# TP4056_18650.net
KiCad netlist of a schematic drawn in EAGLE
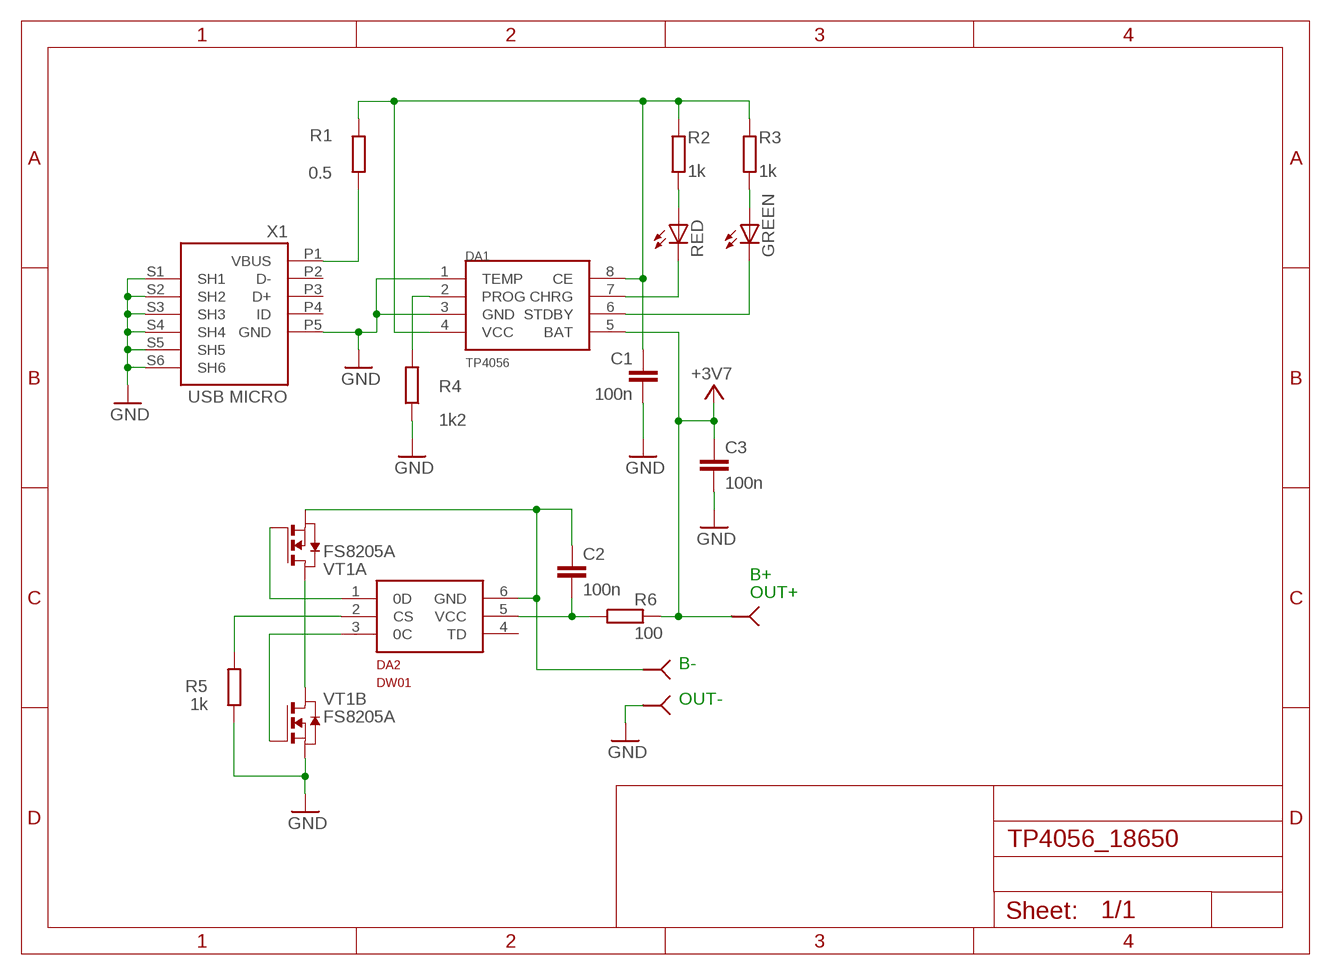
[diagram p0: schematic, sheet 1]

(export (version "E")
  (design (tool "Eeschema 10.0.6"))
  (components
    (comp (ref "B+")
      (value "B-")
      (footprint "eagle-import:PAD-")
      (libsource (lib "eagle-import") (part "B-"))
    )
    (comp (ref "B-")
      (value "B-")
      (footprint "eagle-import:PAD-")
      (libsource (lib "eagle-import") (part "B-"))
    )
    (comp (ref "C1")
      (value "100n")
      (footprint "eagle-import:C0805")
      (libsource (lib "eagle-import") (part "C-EUC0805"))
    )
    (comp (ref "C2")
      (value "100n")
      (footprint "eagle-import:C0805")
      (libsource (lib "eagle-import") (part "C-EUC0805"))
    )
    (comp (ref "C3")
      (value "100n")
      (footprint "eagle-import:C0805")
      (libsource (lib "eagle-import") (part "C-EUC0805"))
    )
    (comp (ref "DA1")
      (value "TP4056")
      (footprint "eagle-import:SOP-8")
      (libsource (lib "eagle-import") (part "TP4056"))
    )
    (comp (ref "DA2")
      (value "DW01A")
      (footprint "eagle-import:SOT23-6")
      (libsource (lib "eagle-import") (part "DW01"))
    )
    (comp (ref "GND")
      (value "B-")
      (footprint "eagle-import:PAD-")
      (libsource (lib "eagle-import") (part "B-"))
    )
    (comp (ref "GREEN")
      (value "LEDCHIP-LED0805")
      (footprint "eagle-import:CHIP-LED0805")
      (libsource (lib "eagle-import") (part "LEDCHIP-LED0805"))
    )
    (comp (ref "R1")
      (value "0.5")
      (footprint "eagle-import:R0805")
      (libsource (lib "eagle-import") (part "R-EU_R0805"))
    )
    (comp (ref "R2")
      (value "1k")
      (footprint "eagle-import:R0805")
      (libsource (lib "eagle-import") (part "R-EU_R0805"))
    )
    (comp (ref "R3")
      (value "1k")
      (footprint "eagle-import:R0805")
      (libsource (lib "eagle-import") (part "R-EU_R0805"))
    )
    (comp (ref "R4")
      (value "1k2")
      (footprint "eagle-import:R0805")
      (libsource (lib "eagle-import") (part "R-EU_R0805"))
    )
    (comp (ref "R5")
      (value "1k")
      (footprint "eagle-import:R0805")
      (libsource (lib "eagle-import") (part "R-EU_R0805"))
    )
    (comp (ref "R6")
      (value "100")
      (footprint "eagle-import:R0805")
      (libsource (lib "eagle-import") (part "R-EU_R0805"))
    )
    (comp (ref "RED")
      (value "LEDCHIP-LED0805")
      (footprint "eagle-import:CHIP-LED0805")
      (libsource (lib "eagle-import") (part "LEDCHIP-LED0805"))
    )
    (comp (ref "VT1")
      (value "FS8205A")
      (footprint "eagle-import:TSSOP-8")
      (libsource (lib "eagle-import") (part "DMN3024LSD"))
    )
    (comp (ref "X1")
      (value "USB MICRO")
      (footprint "eagle-import:CON2_USB_MICRO_B_AT")
      (libsource (lib "eagle-import") (part "MYCON2_USB-MINI-B"))
    )
  )
  (nets
    (net (code "1") (name "+3V7") (class "Default")
      (node (ref "B+") (pin "B-") (pinfunction "B-_B-") (pintype "bidirectional"))
      (node (ref "C3") (pin "1") (pinfunction "1_1") (pintype "passive"))
      (node (ref "DA1") (pin "5") (pinfunction "BAT_5") (pintype "bidirectional"))
      (node (ref "R6") (pin "2") (pinfunction "2_2") (pintype "passive"))
    )
    (net (code "2") (name "GND") (class "Default")
      (node (ref "C1") (pin "2") (pinfunction "2_2") (pintype "passive"))
      (node (ref "C3") (pin "2") (pinfunction "2_2") (pintype "passive"))
      (node (ref "DA1") (pin "1") (pinfunction "TEMP_1") (pintype "bidirectional"))
      (node (ref "DA1") (pin "3") (pinfunction "GND_3") (pintype "bidirectional"))
      (node (ref "GND") (pin "B-") (pinfunction "B-_B-") (pintype "bidirectional"))
      (node (ref "R4") (pin "1") (pinfunction "1_1") (pintype "passive"))
      (node (ref "R5") (pin "1") (pinfunction "1_1") (pintype "passive"))
      (node (ref "VT1") (pin "6") (pinfunction "S_6") (pintype "passive"))
      (node (ref "VT1") (pin "7") (pinfunction "S_7") (pintype "passive"))
      (node (ref "X1") (pin "P5") (pinfunction "GND_P5") (pintype "passive"))
      (node (ref "X1") (pin "S1") (pinfunction "SH1_S1") (pintype "passive"))
      (node (ref "X1") (pin "S2") (pinfunction "SH2_S2") (pintype "passive"))
      (node (ref "X1") (pin "S3") (pinfunction "SH3_S3") (pintype "passive"))
      (node (ref "X1") (pin "S4") (pinfunction "SH4_S4") (pintype "passive"))
      (node (ref "X1") (pin "S5") (pinfunction "SH5_S5") (pintype "passive"))
      (node (ref "X1") (pin "S6") (pinfunction "SH6_S6") (pintype "passive"))
    )
    (net (code "3") (name "Net-(DA1-CE)") (class "Default")
      (node (ref "C1") (pin "1") (pinfunction "1_1") (pintype "passive"))
      (node (ref "DA1") (pin "4") (pinfunction "VCC_4") (pintype "bidirectional"))
      (node (ref "DA1") (pin "8") (pinfunction "CE_8") (pintype "bidirectional"))
      (node (ref "R1") (pin "2") (pinfunction "2_2") (pintype "passive"))
      (node (ref "R2") (pin "2") (pinfunction "2_2") (pintype "passive"))
      (node (ref "R3") (pin "2") (pinfunction "2_2") (pintype "passive"))
    )
    (net (code "4") (name "Net-(DA1-CHRG)") (class "Default")
      (node (ref "DA1") (pin "7") (pinfunction "CHRG_7") (pintype "bidirectional"))
      (node (ref "RED") (pin "C") (pinfunction "C_C") (pintype "passive"))
    )
    (net (code "5") (name "Net-(DA1-PROG)") (class "Default")
      (node (ref "DA1") (pin "2") (pinfunction "PROG_2") (pintype "bidirectional"))
      (node (ref "R4") (pin "2") (pinfunction "2_2") (pintype "passive"))
    )
    (net (code "6") (name "Net-(DA1-STDBY)") (class "Default")
      (node (ref "DA1") (pin "6") (pinfunction "STDBY_6") (pintype "bidirectional"))
      (node (ref "GREEN") (pin "C") (pinfunction "C_C") (pintype "passive"))
    )
    (net (code "7") (name "Net-(DA2-0C)") (class "Default")
      (node (ref "DA2") (pin "3") (pinfunction "0C_3") (pintype "bidirectional"))
      (node (ref "VT1") (pin "5") (pinfunction "G_5") (pintype "passive"))
    )
    (net (code "8") (name "Net-(DA2-0D)") (class "Default")
      (node (ref "DA2") (pin "1") (pinfunction "0D_1") (pintype "bidirectional"))
      (node (ref "VT1") (pin "4") (pinfunction "G_4") (pintype "passive"))
    )
    (net (code "9") (name "Net-(DA2-CS)") (class "Default")
      (node (ref "DA2") (pin "2") (pinfunction "CS_2") (pintype "bidirectional"))
      (node (ref "R5") (pin "2") (pinfunction "2_2") (pintype "passive"))
    )
    (net (code "10") (name "Net-(DA2-GND)") (class "Default")
      (node (ref "B-") (pin "B-") (pinfunction "B-_B-") (pintype "bidirectional"))
      (node (ref "C2") (pin "1") (pinfunction "1_1") (pintype "passive"))
      (node (ref "DA2") (pin "6") (pinfunction "GND_6") (pintype "bidirectional"))
      (node (ref "VT1") (pin "2") (pinfunction "S_2") (pintype "passive"))
      (node (ref "VT1") (pin "3") (pinfunction "S_3") (pintype "passive"))
    )
    (net (code "11") (name "Net-(DA2-VCC)") (class "Default")
      (node (ref "C2") (pin "2") (pinfunction "2_2") (pintype "passive"))
      (node (ref "DA2") (pin "5") (pinfunction "VCC_5") (pintype "bidirectional"))
      (node (ref "R6") (pin "1") (pinfunction "1_1") (pintype "passive"))
    )
    (net (code "12") (name "Net-(GREEN-PadA)") (class "Default")
      (node (ref "GREEN") (pin "A") (pinfunction "A_A") (pintype "passive"))
      (node (ref "R3") (pin "1") (pinfunction "1_1") (pintype "passive"))
    )
    (net (code "13") (name "Net-(R2-Pad1)") (class "Default")
      (node (ref "R2") (pin "1") (pinfunction "1_1") (pintype "passive"))
      (node (ref "RED") (pin "A") (pinfunction "A_A") (pintype "passive"))
    )
    (net (code "14") (name "Net-(VT1A-D)") (class "Default")
      (node (ref "VT1") (pin "1") (pinfunction "D_1") (pintype "passive"))
      (node (ref "VT1") (pin "8") (pinfunction "D_8") (pintype "passive"))
    )
    (net (code "15") (name "Net-(X1-VBUS)") (class "Default")
      (node (ref "R1") (pin "1") (pinfunction "1_1") (pintype "passive"))
      (node (ref "X1") (pin "P1") (pinfunction "VBUS_P1") (pintype "power_in"))
    )
    (net (code "16") (name "unconnected-(DA2-TD-Pad4)") (class "Default")
      (node (ref "DA2") (pin "4") (pinfunction "TD_4") (pintype "bidirectional"))
    )
    (net (code "17") (name "unconnected-(X1-D+-PadP3)") (class "Default")
      (node (ref "X1") (pin "P3") (pinfunction "D+_P3") (pintype "bidirectional"))
    )
    (net (code "18") (name "unconnected-(X1-D--PadP2)") (class "Default")
      (node (ref "X1") (pin "P2") (pinfunction "D-_P2") (pintype "bidirectional"))
    )
    (net (code "19") (name "unconnected-(X1-ID-PadP4)") (class "Default")
      (node (ref "X1") (pin "P4") (pinfunction "ID_P4") (pintype "bidirectional"))
    )
  )
)
